# ESP_IOT.net
KiCad netlist of a schematic drawn in Altium Designer
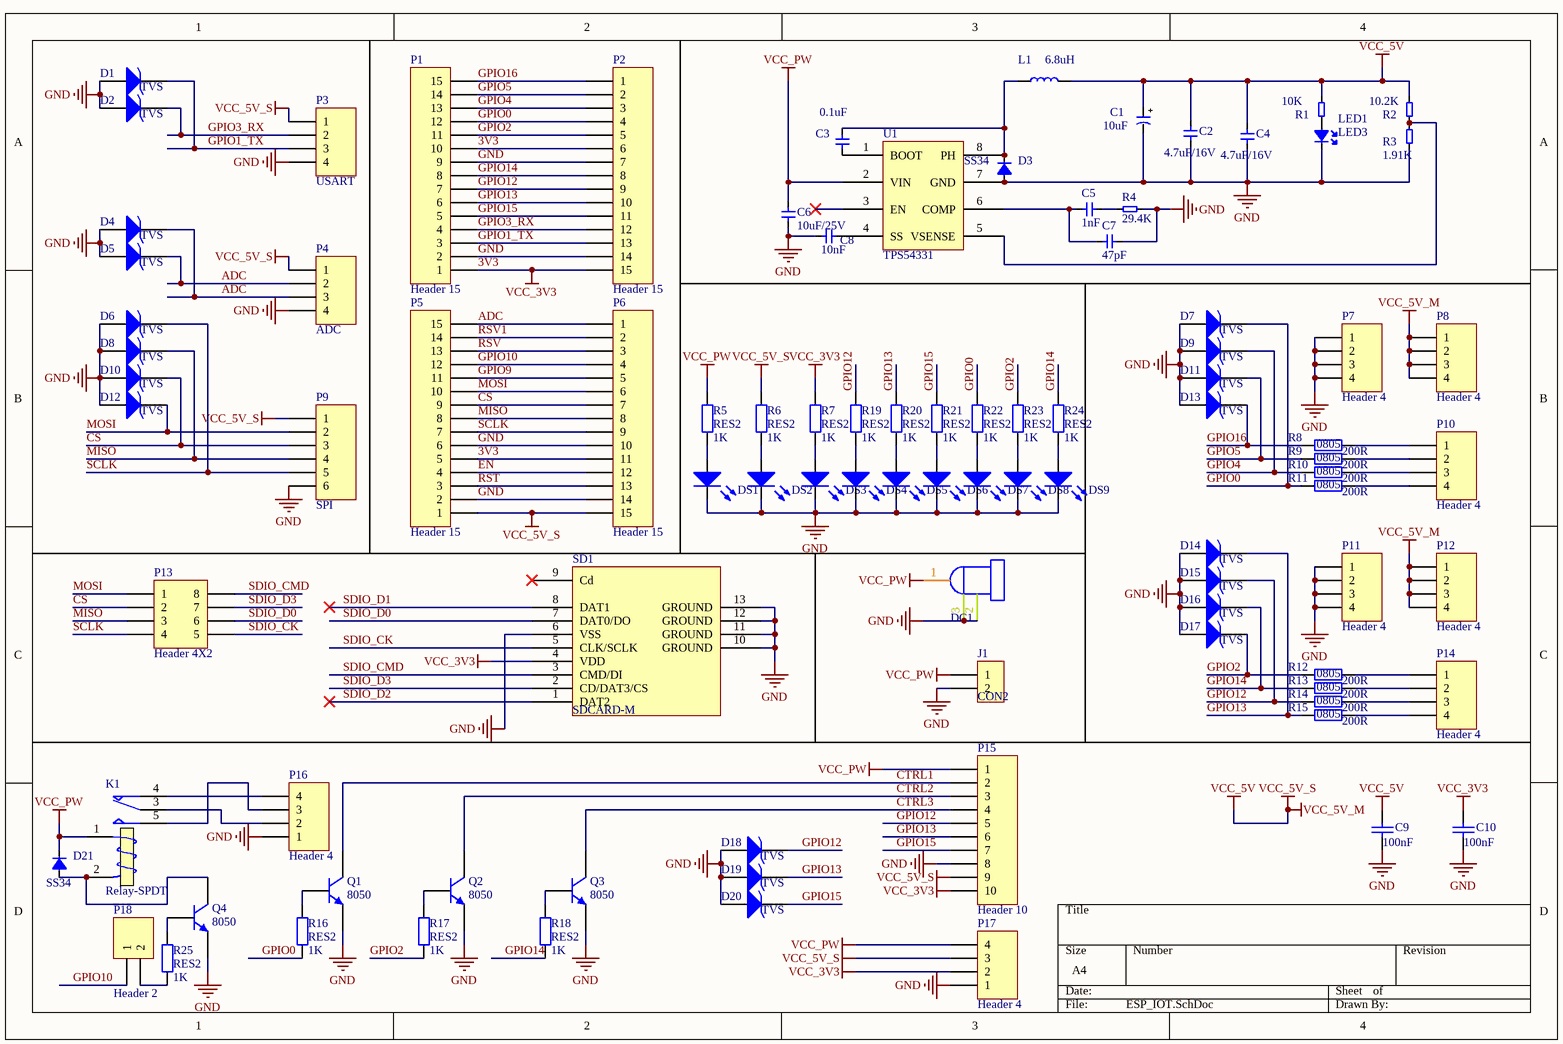
[diagram p0: ESP_IOT.SchDoc]

(export (version "E")
  (design (tool "Eeschema 10.0.6"))
  (components
    (comp (ref "C1")
      (value "10uF")
      (footprint "3528")
      (description "Capacitor")
      (libsource (lib "YHT-SCH") (part "CAP-+"))
    )
    (comp (ref "C2")
      (value "4.7uF/16V")
      (footprint "0603C")
      (description "Capacitor")
      (libsource (lib "YHT-PCB") (part "CAP"))
    )
    (comp (ref "C3")
      (value "0.1uF")
      (footprint "0603C")
      (description "Capacitor")
      (libsource (lib "HXT-SCH") (part "CAP1"))
    )
    (comp (ref "C4")
      (value "4.7uF/16V")
      (footprint "0603C")
      (description "Capacitor")
      (libsource (lib "YHT-PCB") (part "CAP"))
    )
    (comp (ref "C5")
      (value "1nF")
      (footprint "0603C")
      (description "Capacitor")
      (libsource (lib "HXT-SCH") (part "CAP1"))
    )
    (comp (ref "C6")
      (value "10uF/25V")
      (footprint "1206")
      (description "Capacitor")
      (libsource (lib "HXT-SCH") (part "CAP1"))
    )
    (comp (ref "C7")
      (value "47pF")
      (footprint "0603C")
      (description "Capacitor")
      (libsource (lib "YHT-PCB") (part "CAP"))
    )
    (comp (ref "C8")
      (value "10nF")
      (footprint "0603C")
      (description "Capacitor")
      (libsource (lib "YHT-PCB") (part "CAP"))
    )
    (comp (ref "C9")
      (value "100nF")
      (footprint "C 0603_L")
      (fields (field (name "Comment") "CAP"))
      (libsource (lib "QT") (part "CAP"))
    )
    (comp (ref "C10")
      (value "100nF")
      (footprint "C 0603_L")
      (fields (field (name "Comment") "CAP"))
      (libsource (lib "QT") (part "CAP"))
    )
    (comp (ref "D1")
      (value "TVS")
      (footprint "SOD-523")
      (description "High Conductance Fast Diode")
      (fields (field (name "PUBLISHER") "Altium Limited"))
      (libsource (lib "QT") (part "D"))
    )
    (comp (ref "D2")
      (value "TVS")
      (footprint "SOD-523")
      (description "High Conductance Fast Diode")
      (fields (field (name "PUBLISHER") "Altium Limited"))
      (libsource (lib "QT") (part "D"))
    )
    (comp (ref "D3")
      (value "SS34")
      (footprint "DO-214AC-SMA")
      (description "DIODE LED")
      (libsource (lib "HXT-SCH") (part "DIOLED_1"))
    )
    (comp (ref "D4")
      (value "TVS")
      (footprint "SOD-523")
      (description "High Conductance Fast Diode")
      (fields (field (name "PUBLISHER") "Altium Limited"))
      (libsource (lib "QT") (part "D"))
    )
    (comp (ref "D5")
      (value "TVS")
      (footprint "SOD-523")
      (description "High Conductance Fast Diode")
      (fields (field (name "PUBLISHER") "Altium Limited"))
      (libsource (lib "QT") (part "D"))
    )
    (comp (ref "D6")
      (value "TVS")
      (footprint "SOD-523")
      (description "High Conductance Fast Diode")
      (fields (field (name "PUBLISHER") "Altium Limited"))
      (libsource (lib "QT") (part "D"))
    )
    (comp (ref "D7")
      (value "TVS")
      (footprint "SOD-523")
      (description "High Conductance Fast Diode")
      (fields (field (name "PUBLISHER") "Altium Limited"))
      (libsource (lib "QT") (part "D"))
    )
    (comp (ref "D8")
      (value "TVS")
      (footprint "SOD-523")
      (description "High Conductance Fast Diode")
      (fields (field (name "PUBLISHER") "Altium Limited"))
      (libsource (lib "QT") (part "D"))
    )
    (comp (ref "D9")
      (value "TVS")
      (footprint "SOD-523")
      (description "High Conductance Fast Diode")
      (fields (field (name "PUBLISHER") "Altium Limited"))
      (libsource (lib "QT") (part "D"))
    )
    (comp (ref "D10")
      (value "TVS")
      (footprint "SOD-523")
      (description "High Conductance Fast Diode")
      (fields (field (name "PUBLISHER") "Altium Limited"))
      (libsource (lib "QT") (part "D"))
    )
    (comp (ref "D11")
      (value "TVS")
      (footprint "SOD-523")
      (description "High Conductance Fast Diode")
      (fields (field (name "PUBLISHER") "Altium Limited"))
      (libsource (lib "QT") (part "D"))
    )
    (comp (ref "D12")
      (value "TVS")
      (footprint "SOD-523")
      (description "High Conductance Fast Diode")
      (fields (field (name "PUBLISHER") "Altium Limited"))
      (libsource (lib "QT") (part "D"))
    )
    (comp (ref "D13")
      (value "TVS")
      (footprint "SOD-523")
      (description "High Conductance Fast Diode")
      (fields (field (name "PUBLISHER") "Altium Limited"))
      (libsource (lib "QT") (part "D"))
    )
    (comp (ref "D14")
      (value "TVS")
      (footprint "SOD-523")
      (description "High Conductance Fast Diode")
      (fields (field (name "PUBLISHER") "Altium Limited"))
      (libsource (lib "QT") (part "D"))
    )
    (comp (ref "D15")
      (value "TVS")
      (footprint "SOD-523")
      (description "High Conductance Fast Diode")
      (fields (field (name "PUBLISHER") "Altium Limited"))
      (libsource (lib "QT") (part "D"))
    )
    (comp (ref "D16")
      (value "TVS")
      (footprint "SOD-523")
      (description "High Conductance Fast Diode")
      (fields (field (name "PUBLISHER") "Altium Limited"))
      (libsource (lib "QT") (part "D"))
    )
    (comp (ref "D17")
      (value "TVS")
      (footprint "SOD-523")
      (description "High Conductance Fast Diode")
      (fields (field (name "PUBLISHER") "Altium Limited"))
      (libsource (lib "QT") (part "D"))
    )
    (comp (ref "D18")
      (value "TVS")
      (footprint "SOD-523")
      (description "High Conductance Fast Diode")
      (fields (field (name "PUBLISHER") "Altium Limited"))
      (libsource (lib "QT") (part "D"))
    )
    (comp (ref "D19")
      (value "TVS")
      (footprint "SOD-523")
      (description "High Conductance Fast Diode")
      (fields (field (name "PUBLISHER") "Altium Limited"))
      (libsource (lib "QT") (part "D"))
    )
    (comp (ref "D20")
      (value "TVS")
      (footprint "SOD-523")
      (description "High Conductance Fast Diode")
      (fields (field (name "PUBLISHER") "Altium Limited"))
      (libsource (lib "QT") (part "D"))
    )
    (comp (ref "D21")
      (value "SS34")
      (footprint "DO-214AC-SMA")
      (description "DIODE LED")
      (libsource (lib "HXT-SCH") (part "DIOLED_1"))
    )
    (comp (ref "DC1") (value "DC") (footprint "DC-005") (libsource (lib "QT") (part "DC")))
    (comp (ref "DS1") (value "LED") (footprint "LED 0805B") (libsource (lib "QT") (part "LED")))
    (comp (ref "DS2") (value "LED") (footprint "LED 0805B") (libsource (lib "QT") (part "LED")))
    (comp (ref "DS3") (value "LED") (footprint "LED 0805B") (libsource (lib "QT") (part "LED")))
    (comp (ref "DS4") (value "LED") (footprint "LED 0805B") (libsource (lib "QT") (part "LED")))
    (comp (ref "DS5") (value "LED") (footprint "LED 0805B") (libsource (lib "QT") (part "LED")))
    (comp (ref "DS6") (value "LED") (footprint "LED 0805B") (libsource (lib "QT") (part "LED")))
    (comp (ref "DS7") (value "LED") (footprint "LED 0805B") (libsource (lib "QT") (part "LED")))
    (comp (ref "DS8") (value "LED") (footprint "LED 0805B") (libsource (lib "QT") (part "LED")))
    (comp (ref "DS9") (value "LED") (footprint "LED 0805B") (libsource (lib "QT") (part "LED")))
    (comp (ref "J1") (value "CON2") (footprint "DG1282-5.0") (libsource (lib "常用元件库") (part "CON2")))
    (comp (ref "K1")
      (value "Relay-SPDT")
      (footprint "SRD-C_B")
      (description "Single-Pole Dual-Throw Relay")
      (fields (field (name "PUBLISHER") "Altium Limited"))
      (libsource (lib "QT") (part "Relay-SPDT"))
    )
    (comp (ref "L1") (value "6.8uH") (footprint "L100") (libsource (lib "HXT-SCH") (part "INDUCTOR1_1")))
    (comp (ref "LED1")
      (value "LED3")
      (footprint "0603-led")
      (description "DIODE LED")
      (libsource (lib "HXT-SCH") (part "CP_DIOLED"))
    )
    (comp (ref "P1")
      (value "Header 15")
      (footprint "HDR1X15")
      (description "Header, 15-Pin")
      (fields (field (name "PUBLISHER") "Altium Limited"))
      (libsource (lib "Miscellaneous Connectors") (part "Header 15"))
    )
    (comp (ref "P2")
      (value "Header 15")
      (footprint "HDR1X15")
      (description "Header, 15-Pin")
      (fields (field (name "PUBLISHER") "Altium Limited"))
      (libsource (lib "") (part "Header 15_1"))
    )
    (comp (ref "P3")
      (value "USART")
      (footprint "KF2EDGK-2.54-WI-4P")
      (description "Header, 4-Pin")
      (fields (field (name "PUBLISHER") "Altium Limited"))
      (libsource (lib "QT") (part "Header 4"))
    )
    (comp (ref "P4")
      (value "ADC")
      (footprint "KF2EDGK-2.54-WI-4P")
      (description "Header, 4-Pin")
      (fields (field (name "PUBLISHER") "Altium Limited"))
      (libsource (lib "QT") (part "Header 4"))
    )
    (comp (ref "P5")
      (value "Header 15")
      (footprint "HDR1X15")
      (description "Header, 15-Pin")
      (fields (field (name "PUBLISHER") "Altium Limited"))
      (libsource (lib "Miscellaneous Connectors") (part "Header 15"))
    )
    (comp (ref "P6")
      (value "Header 15")
      (footprint "HDR1X15")
      (description "Header, 15-Pin")
      (fields (field (name "PUBLISHER") "Altium Limited"))
      (libsource (lib "") (part "Header 15_1"))
    )
    (comp (ref "P7")
      (value "Header 4")
      (footprint "HDR2.54-LI-4P")
      (description "Header, 4-Pin")
      (fields (field (name "PUBLISHER") "Altium Limited"))
      (libsource (lib "QT") (part "Header 4"))
    )
    (comp (ref "P8")
      (value "Header 4")
      (footprint "HDR2.54-LI-4P")
      (description "Header, 4-Pin")
      (fields (field (name "PUBLISHER") "Altium Limited"))
      (libsource (lib "QT") (part "Header 4"))
    )
    (comp (ref "P9")
      (value "SPI")
      (footprint "KF2EDGK-2.54-WI-6P")
      (description "Header, 6-Pin")
      (fields (field (name "PUBLISHER") "Altium Limited"))
      (libsource (lib "Miscellaneous Connectors") (part "Header 6"))
    )
    (comp (ref "P10")
      (value "Header 4")
      (footprint "HDR2.54-LI-4P")
      (description "Header, 4-Pin")
      (fields (field (name "PUBLISHER") "Altium Limited"))
      (libsource (lib "QT") (part "Header 4"))
    )
    (comp (ref "P11")
      (value "Header 4")
      (footprint "HDR2.54-LI-4P")
      (description "Header, 4-Pin")
      (fields (field (name "PUBLISHER") "Altium Limited"))
      (libsource (lib "QT") (part "Header 4"))
    )
    (comp (ref "P12")
      (value "Header 4")
      (footprint "HDR2.54-LI-4P")
      (description "Header, 4-Pin")
      (fields (field (name "PUBLISHER") "Altium Limited"))
      (libsource (lib "QT") (part "Header 4"))
    )
    (comp (ref "P13")
      (value "Header 4X2")
      (footprint "CSW1.27 SMD-4P")
      (description "Header, 4-Pin, Dual row")
      (fields (field (name "PUBLISHER") "Altium Limited"))
      (libsource (lib "QT") (part "Header 4X2"))
    )
    (comp (ref "P14")
      (value "Header 4")
      (footprint "HDR2.54-LI-4P")
      (description "Header, 4-Pin")
      (fields (field (name "PUBLISHER") "Altium Limited"))
      (libsource (lib "QT") (part "Header 4"))
    )
    (comp (ref "P15")
      (value "Header 10")
      (footprint "KF2EDGK-2.54-WI-10P")
      (description "Header, 10-Pin")
      (fields (field (name "PUBLISHER") "Altium Limited"))
      (libsource (lib "Miscellaneous Connectors") (part "Header 10"))
    )
    (comp (ref "P16")
      (value "Header 4")
      (footprint "COM4_8")
      (description "Header, 4-Pin")
      (fields (field (name "PUBLISHER") "Altium Limited"))
      (libsource (lib "Miscellaneous Connectors") (part "Header 4"))
    )
    (comp (ref "P17")
      (value "Header 4")
      (footprint "COM4_8")
      (description "Header, 4-Pin")
      (fields (field (name "PUBLISHER") "Altium Limited"))
      (libsource (lib "Miscellaneous Connectors") (part "Header 4"))
    )
    (comp (ref "P18")
      (value "Header 2")
      (footprint "HDR2.54-LI-2P")
      (description "Header, 2-Pin")
      (fields (field (name "PUBLISHER") "Altium Limited"))
      (libsource (lib "QT") (part "Header 2"))
    )
    (comp (ref "Q1")
      (value "8050")
      (footprint "SOT23-3L")
      (description "NPN Bipolar Transistor")
      (fields (field (name "PUBLISHER") "Altium Limited"))
      (libsource (lib "QT") (part "NPN  SOT"))
    )
    (comp (ref "Q2")
      (value "8050")
      (footprint "SOT23-3L")
      (description "NPN Bipolar Transistor")
      (fields (field (name "PUBLISHER") "Altium Limited"))
      (libsource (lib "QT") (part "NPN  SOT"))
    )
    (comp (ref "Q3")
      (value "8050")
      (footprint "SOT23-3L")
      (description "NPN Bipolar Transistor")
      (fields (field (name "PUBLISHER") "Altium Limited"))
      (libsource (lib "QT") (part "NPN  SOT"))
    )
    (comp (ref "Q4")
      (value "8050")
      (footprint "SOT23-3L")
      (description "NPN Bipolar Transistor")
      (fields (field (name "PUBLISHER") "Altium Limited"))
      (libsource (lib "QT") (part "NPN  SOT"))
    )
    (comp (ref "R1") (value "10K") (footprint "0603") (libsource (lib "HXT-SCH") (part "RES2")))
    (comp (ref "R2") (value "10.2K") (footprint "0603") (libsource (lib "HXT-SCH") (part "RES2")))
    (comp (ref "R3") (value "1.91K") (footprint "0603") (libsource (lib "HXT-SCH") (part "RES2")))
    (comp (ref "R4") (value "29.4K") (footprint "0603") (libsource (lib "HXT-SCH") (part "RES2")))
    (comp (ref "R5")
      (value "RES2")
      (footprint "R 0805_L")
      (description "Resistor")
      (fields (field (name "ALTIUM_VALUE") "1K") (field (name "PUBLISHER") "Altium Limited"))
      (libsource (lib "") (part "RES2_1"))
    )
    (comp (ref "R6")
      (value "RES2")
      (footprint "R 0805_L")
      (description "Resistor")
      (fields (field (name "ALTIUM_VALUE") "1K") (field (name "PUBLISHER") "Altium Limited"))
      (libsource (lib "") (part "RES2_1"))
    )
    (comp (ref "R7")
      (value "RES2")
      (footprint "R 0805_L")
      (description "Resistor")
      (fields (field (name "ALTIUM_VALUE") "1K") (field (name "PUBLISHER") "Altium Limited"))
      (libsource (lib "") (part "RES2_1"))
    )
    (comp (ref "R8")
      (value "0805")
      (footprint "R 0805_L")
      (description "Resistor")
      (fields (field (name "ALTIUM_VALUE") "200R") (field (name "PUBLISHER") "Altium Limited"))
      (libsource (lib "") (part "RES2_2"))
    )
    (comp (ref "R9")
      (value "0805")
      (footprint "R 0805_L")
      (description "Resistor")
      (fields (field (name "ALTIUM_VALUE") "200R") (field (name "PUBLISHER") "Altium Limited"))
      (libsource (lib "") (part "RES2_2"))
    )
    (comp (ref "R10")
      (value "0805")
      (footprint "R 0805_L")
      (description "Resistor")
      (fields (field (name "ALTIUM_VALUE") "200R") (field (name "PUBLISHER") "Altium Limited"))
      (libsource (lib "") (part "RES2_2"))
    )
    (comp (ref "R11")
      (value "0805")
      (footprint "R 0805_L")
      (description "Resistor")
      (fields (field (name "ALTIUM_VALUE") "200R") (field (name "PUBLISHER") "Altium Limited"))
      (libsource (lib "") (part "RES2_2"))
    )
    (comp (ref "R12")
      (value "0805")
      (footprint "R 0805_L")
      (description "Resistor")
      (fields (field (name "ALTIUM_VALUE") "200R") (field (name "PUBLISHER") "Altium Limited"))
      (libsource (lib "") (part "RES2_2"))
    )
    (comp (ref "R13")
      (value "0805")
      (footprint "R 0805_L")
      (description "Resistor")
      (fields (field (name "ALTIUM_VALUE") "200R") (field (name "PUBLISHER") "Altium Limited"))
      (libsource (lib "") (part "RES2_2"))
    )
    (comp (ref "R14")
      (value "0805")
      (footprint "R 0805_L")
      (description "Resistor")
      (fields (field (name "ALTIUM_VALUE") "200R") (field (name "PUBLISHER") "Altium Limited"))
      (libsource (lib "") (part "RES2_2"))
    )
    (comp (ref "R15")
      (value "0805")
      (footprint "R 0805_L")
      (description "Resistor")
      (fields (field (name "ALTIUM_VALUE") "200R") (field (name "PUBLISHER") "Altium Limited"))
      (libsource (lib "") (part "RES2_2"))
    )
    (comp (ref "R16")
      (value "RES2")
      (footprint "R 0805_L")
      (description "Resistor")
      (fields (field (name "ALTIUM_VALUE") "1K") (field (name "PUBLISHER") "Altium Limited"))
      (libsource (lib "QT") (part "RES2"))
    )
    (comp (ref "R17")
      (value "RES2")
      (footprint "R 0805_L")
      (description "Resistor")
      (fields (field (name "ALTIUM_VALUE") "1K") (field (name "PUBLISHER") "Altium Limited"))
      (libsource (lib "QT") (part "RES2"))
    )
    (comp (ref "R18")
      (value "RES2")
      (footprint "R 0805_L")
      (description "Resistor")
      (fields (field (name "ALTIUM_VALUE") "1K") (field (name "PUBLISHER") "Altium Limited"))
      (libsource (lib "QT") (part "RES2"))
    )
    (comp (ref "R19")
      (value "RES2")
      (footprint "R 0805_L")
      (description "Resistor")
      (fields (field (name "ALTIUM_VALUE") "1K") (field (name "PUBLISHER") "Altium Limited"))
      (libsource (lib "") (part "RES2_1"))
    )
    (comp (ref "R20")
      (value "RES2")
      (footprint "R 0805_L")
      (description "Resistor")
      (fields (field (name "ALTIUM_VALUE") "1K") (field (name "PUBLISHER") "Altium Limited"))
      (libsource (lib "") (part "RES2_1"))
    )
    (comp (ref "R21")
      (value "RES2")
      (footprint "R 0805_L")
      (description "Resistor")
      (fields (field (name "ALTIUM_VALUE") "1K") (field (name "PUBLISHER") "Altium Limited"))
      (libsource (lib "") (part "RES2_1"))
    )
    (comp (ref "R22")
      (value "RES2")
      (footprint "R 0805_L")
      (description "Resistor")
      (fields (field (name "ALTIUM_VALUE") "1K") (field (name "PUBLISHER") "Altium Limited"))
      (libsource (lib "") (part "RES2_1"))
    )
    (comp (ref "R23")
      (value "RES2")
      (footprint "R 0805_L")
      (description "Resistor")
      (fields (field (name "ALTIUM_VALUE") "1K") (field (name "PUBLISHER") "Altium Limited"))
      (libsource (lib "") (part "RES2_1"))
    )
    (comp (ref "R24")
      (value "RES2")
      (footprint "R 0805_L")
      (description "Resistor")
      (fields (field (name "ALTIUM_VALUE") "1K") (field (name "PUBLISHER") "Altium Limited"))
      (libsource (lib "") (part "RES2_1"))
    )
    (comp (ref "R25")
      (value "RES2")
      (footprint "R 0805_L")
      (description "Resistor")
      (fields (field (name "ALTIUM_VALUE") "1K") (field (name "PUBLISHER") "Altium Limited"))
      (libsource (lib "QT") (part "RES2"))
    )
    (comp (ref "SD1")
      (value "SDCARD-M")
      (footprint "SDCARD-M")
      (description "TF卡槽")
      (libsource (lib "Fszhang") (part "SDCARD-M"))
    )
    (comp (ref "U1") (value "TPS54331") (footprint "SO08") (libsource (lib "YHT-SCH") (part "TPS54331")))
  )
  (nets
    (net (code "1") (name "/ADC") (class "Default")
      (node (ref "D4") (pin "2") (pinfunction "K_2") (pintype "passive"))
      (node (ref "D5") (pin "2") (pinfunction "K_2") (pintype "passive"))
      (node (ref "P4") (pin "2") (pinfunction "2_2") (pintype "passive"))
      (node (ref "P4") (pin "3") (pinfunction "3_3") (pintype "passive"))
      (node (ref "P5") (pin "15") (pinfunction "15_15") (pintype "passive"))
      (node (ref "P6") (pin "1") (pinfunction "1_1") (pintype "passive"))
    )
    (net (code "2") (name "/CS") (class "Default")
      (node (ref "D10") (pin "2") (pinfunction "K_2") (pintype "passive"))
      (node (ref "P13") (pin "2") (pinfunction "2_2") (pintype "passive"))
      (node (ref "P5") (pin "9") (pinfunction "9_9") (pintype "passive"))
      (node (ref "P6") (pin "7") (pinfunction "7_7") (pintype "passive"))
      (node (ref "P9") (pin "3") (pinfunction "3_3") (pintype "passive"))
    )
    (net (code "3") (name "/CTRL1") (class "Default")
      (node (ref "P15") (pin "2") (pinfunction "2_2") (pintype "passive"))
      (node (ref "Q1") (pin "3") (pinfunction "C_3") (pintype "passive"))
    )
    (net (code "4") (name "/CTRL2") (class "Default")
      (node (ref "P15") (pin "3") (pinfunction "3_3") (pintype "passive"))
      (node (ref "Q2") (pin "3") (pinfunction "C_3") (pintype "passive"))
    )
    (net (code "5") (name "/CTRL3") (class "Default")
      (node (ref "P15") (pin "4") (pinfunction "4_4") (pintype "passive"))
      (node (ref "Q3") (pin "3") (pinfunction "C_3") (pintype "passive"))
    )
    (net (code "6") (name "/EN") (class "Default")
      (node (ref "P5") (pin "4") (pinfunction "4_4") (pintype "passive"))
      (node (ref "P6") (pin "12") (pinfunction "12_12") (pintype "passive"))
    )
    (net (code "7") (name "/GPIO0") (class "Default")
      (node (ref "D7") (pin "2") (pinfunction "K_2") (pintype "passive"))
      (node (ref "P1") (pin "12") (pinfunction "12_12") (pintype "passive"))
      (node (ref "P2") (pin "4") (pinfunction "4_4") (pintype "passive"))
      (node (ref "R11") (pin "1") (pinfunction "1_1") (pintype "passive"))
      (node (ref "R16") (pin "2") (pinfunction "2_2") (pintype "passive"))
      (node (ref "R22") (pin "2") (pinfunction "2_2") (pintype "passive"))
    )
    (net (code "8") (name "/GPIO1_TX") (class "Default")
      (node (ref "D1") (pin "2") (pinfunction "K_2") (pintype "passive"))
      (node (ref "P1") (pin "3") (pinfunction "3_3") (pintype "passive"))
      (node (ref "P2") (pin "13") (pinfunction "13_13") (pintype "passive"))
      (node (ref "P3") (pin "3") (pinfunction "3_3") (pintype "passive"))
    )
    (net (code "9") (name "/GPIO2") (class "Default")
      (node (ref "D17") (pin "2") (pinfunction "K_2") (pintype "passive"))
      (node (ref "P1") (pin "11") (pinfunction "11_11") (pintype "passive"))
      (node (ref "P2") (pin "5") (pinfunction "5_5") (pintype "passive"))
      (node (ref "R12") (pin "1") (pinfunction "1_1") (pintype "passive"))
      (node (ref "R17") (pin "2") (pinfunction "2_2") (pintype "passive"))
      (node (ref "R23") (pin "2") (pinfunction "2_2") (pintype "passive"))
    )
    (net (code "10") (name "/GPIO3_RX") (class "Default")
      (node (ref "D2") (pin "2") (pinfunction "K_2") (pintype "passive"))
      (node (ref "P1") (pin "4") (pinfunction "4_4") (pintype "passive"))
      (node (ref "P2") (pin "12") (pinfunction "12_12") (pintype "passive"))
      (node (ref "P3") (pin "2") (pinfunction "2_2") (pintype "passive"))
    )
    (net (code "11") (name "/GPIO4") (class "Default")
      (node (ref "D9") (pin "2") (pinfunction "K_2") (pintype "passive"))
      (node (ref "P1") (pin "13") (pinfunction "13_13") (pintype "passive"))
      (node (ref "P2") (pin "3") (pinfunction "3_3") (pintype "passive"))
      (node (ref "R10") (pin "1") (pinfunction "1_1") (pintype "passive"))
    )
    (net (code "12") (name "/GPIO5") (class "Default")
      (node (ref "D11") (pin "2") (pinfunction "K_2") (pintype "passive"))
      (node (ref "P1") (pin "14") (pinfunction "14_14") (pintype "passive"))
      (node (ref "P2") (pin "2") (pinfunction "2_2") (pintype "passive"))
      (node (ref "R9") (pin "1") (pinfunction "1_1") (pintype "passive"))
    )
    (net (code "13") (name "/GPIO9") (class "Default")
      (node (ref "P5") (pin "11") (pinfunction "11_11") (pintype "passive"))
      (node (ref "P6") (pin "5") (pinfunction "5_5") (pintype "passive"))
    )
    (net (code "14") (name "/GPIO10") (class "Default")
      (node (ref "P18") (pin "1") (pinfunction "1_1") (pintype "passive"))
      (node (ref "P5") (pin "12") (pinfunction "12_12") (pintype "passive"))
      (node (ref "P6") (pin "4") (pinfunction "4_4") (pintype "passive"))
    )
    (net (code "15") (name "/GPIO12") (class "Default")
      (node (ref "D15") (pin "2") (pinfunction "K_2") (pintype "passive"))
      (node (ref "D18") (pin "2") (pinfunction "K_2") (pintype "passive"))
      (node (ref "P1") (pin "7") (pinfunction "7_7") (pintype "passive"))
      (node (ref "P15") (pin "5") (pinfunction "5_5") (pintype "passive"))
      (node (ref "P2") (pin "9") (pinfunction "9_9") (pintype "passive"))
      (node (ref "R14") (pin "1") (pinfunction "1_1") (pintype "passive"))
      (node (ref "R19") (pin "2") (pinfunction "2_2") (pintype "passive"))
    )
    (net (code "16") (name "/GPIO13") (class "Default")
      (node (ref "D14") (pin "2") (pinfunction "K_2") (pintype "passive"))
      (node (ref "D19") (pin "2") (pinfunction "K_2") (pintype "passive"))
      (node (ref "P1") (pin "6") (pinfunction "6_6") (pintype "passive"))
      (node (ref "P15") (pin "6") (pinfunction "6_6") (pintype "passive"))
      (node (ref "P2") (pin "10") (pinfunction "10_10") (pintype "passive"))
      (node (ref "R15") (pin "1") (pinfunction "1_1") (pintype "passive"))
      (node (ref "R20") (pin "2") (pinfunction "2_2") (pintype "passive"))
    )
    (net (code "17") (name "/GPIO14") (class "Default")
      (node (ref "D16") (pin "2") (pinfunction "K_2") (pintype "passive"))
      (node (ref "P1") (pin "8") (pinfunction "8_8") (pintype "passive"))
      (node (ref "P2") (pin "8") (pinfunction "8_8") (pintype "passive"))
      (node (ref "R13") (pin "1") (pinfunction "1_1") (pintype "passive"))
      (node (ref "R18") (pin "2") (pinfunction "2_2") (pintype "passive"))
      (node (ref "R24") (pin "2") (pinfunction "2_2") (pintype "passive"))
    )
    (net (code "18") (name "/GPIO15") (class "Default")
      (node (ref "D20") (pin "2") (pinfunction "K_2") (pintype "passive"))
      (node (ref "P1") (pin "5") (pinfunction "5_5") (pintype "passive"))
      (node (ref "P15") (pin "7") (pinfunction "7_7") (pintype "passive"))
      (node (ref "P2") (pin "11") (pinfunction "11_11") (pintype "passive"))
      (node (ref "R21") (pin "2") (pinfunction "2_2") (pintype "passive"))
    )
    (net (code "19") (name "/GPIO16") (class "Default")
      (node (ref "D13") (pin "2") (pinfunction "K_2") (pintype "passive"))
      (node (ref "P1") (pin "15") (pinfunction "15_15") (pintype "passive"))
      (node (ref "P2") (pin "1") (pinfunction "1_1") (pintype "passive"))
      (node (ref "R8") (pin "1") (pinfunction "1_1") (pintype "passive"))
    )
    (net (code "20") (name "/MISO") (class "Default")
      (node (ref "D8") (pin "2") (pinfunction "K_2") (pintype "passive"))
      (node (ref "P13") (pin "3") (pinfunction "3_3") (pintype "passive"))
      (node (ref "P5") (pin "8") (pinfunction "8_8") (pintype "passive"))
      (node (ref "P6") (pin "8") (pinfunction "8_8") (pintype "passive"))
      (node (ref "P9") (pin "4") (pinfunction "4_4") (pintype "passive"))
    )
    (net (code "21") (name "/MOSI") (class "Default")
      (node (ref "D12") (pin "2") (pinfunction "K_2") (pintype "passive"))
      (node (ref "P13") (pin "1") (pinfunction "1_1") (pintype "passive"))
      (node (ref "P5") (pin "10") (pinfunction "10_10") (pintype "passive"))
      (node (ref "P6") (pin "6") (pinfunction "6_6") (pintype "passive"))
      (node (ref "P9") (pin "2") (pinfunction "2_2") (pintype "passive"))
    )
    (net (code "22") (name "/RST") (class "Default")
      (node (ref "P5") (pin "3") (pinfunction "3_3") (pintype "passive"))
      (node (ref "P6") (pin "13") (pinfunction "13_13") (pintype "passive"))
    )
    (net (code "23") (name "/RSV") (class "Default")
      (node (ref "P5") (pin "13") (pinfunction "13_13") (pintype "passive"))
      (node (ref "P6") (pin "3") (pinfunction "3_3") (pintype "passive"))
    )
    (net (code "24") (name "/RSV1") (class "Default")
      (node (ref "P5") (pin "14") (pinfunction "14_14") (pintype "passive"))
      (node (ref "P6") (pin "2") (pinfunction "2_2") (pintype "passive"))
    )
    (net (code "25") (name "/SCLK") (class "Default")
      (node (ref "D6") (pin "2") (pinfunction "K_2") (pintype "passive"))
      (node (ref "P13") (pin "4") (pinfunction "4_4") (pintype "passive"))
      (node (ref "P5") (pin "7") (pinfunction "7_7") (pintype "passive"))
      (node (ref "P6") (pin "9") (pinfunction "9_9") (pintype "passive"))
      (node (ref "P9") (pin "5") (pinfunction "5_5") (pintype "passive"))
    )
    (net (code "26") (name "/SDIO_CK") (class "Default")
      (node (ref "P13") (pin "5") (pinfunction "5_5") (pintype "passive"))
      (node (ref "SD1") (pin "5") (pinfunction "CLK/SCLK_5") (pintype "passive"))
    )
    (net (code "27") (name "/SDIO_CMD") (class "Default")
      (node (ref "P13") (pin "8") (pinfunction "8_8") (pintype "passive"))
      (node (ref "SD1") (pin "3") (pinfunction "CMD/DI_3") (pintype "passive"))
    )
    (net (code "28") (name "/SDIO_D0") (class "Default")
      (node (ref "P13") (pin "6") (pinfunction "6_6") (pintype "passive"))
      (node (ref "SD1") (pin "7") (pinfunction "DAT0/DO_7") (pintype "passive"))
    )
    (net (code "29") (name "/SDIO_D1") (class "Default")
      (node (ref "SD1") (pin "8") (pinfunction "DAT1_8") (pintype "passive+no_connect"))
    )
    (net (code "30") (name "/SDIO_D2") (class "Default")
      (node (ref "SD1") (pin "1") (pinfunction "DAT2_1") (pintype "passive+no_connect"))
    )
    (net (code "31") (name "/SDIO_D3") (class "Default")
      (node (ref "P13") (pin "7") (pinfunction "7_7") (pintype "passive"))
      (node (ref "SD1") (pin "2") (pinfunction "CD/DAT3/CS_2") (pintype "passive"))
    )
    (net (code "32") (name "GND") (class "Default")
      (node (ref "C1") (pin "2") (pinfunction "2_2") (pintype "passive"))
      (node (ref "C10") (pin "1") (pinfunction "1_1") (pintype "passive"))
      (node (ref "C2") (pin "1") (pinfunction "1_1") (pintype "passive"))
      (node (ref "C4") (pin "1") (pinfunction "1_1") (pintype "passive"))
      (node (ref "C6") (pin "1") (pinfunction "1_1") (pintype "passive"))
      (node (ref "C7") (pin "2") (pinfunction "2_2") (pintype "passive"))
      (node (ref "C8") (pin "2") (pinfunction "2_2") (pintype "passive"))
      (node (ref "C9") (pin "1") (pinfunction "1_1") (pintype "passive"))
      (node (ref "D1") (pin "1") (pinfunction "A_1") (pintype "passive"))
      (node (ref "D10") (pin "1") (pinfunction "A_1") (pintype "passive"))
      (node (ref "D11") (pin "1") (pinfunction "A_1") (pintype "passive"))
      (node (ref "D12") (pin "1") (pinfunction "A_1") (pintype "passive"))
      (node (ref "D13") (pin "1") (pinfunction "A_1") (pintype "passive"))
      (node (ref "D14") (pin "1") (pinfunction "A_1") (pintype "passive"))
      (node (ref "D15") (pin "1") (pinfunction "A_1") (pintype "passive"))
      (node (ref "D16") (pin "1") (pinfunction "A_1") (pintype "passive"))
      (node (ref "D17") (pin "1") (pinfunction "A_1") (pintype "passive"))
      (node (ref "D18") (pin "1") (pinfunction "A_1") (pintype "passive"))
      (node (ref "D19") (pin "1") (pinfunction "A_1") (pintype "passive"))
      (node (ref "D2") (pin "1") (pinfunction "A_1") (pintype "passive"))
      (node (ref "D20") (pin "1") (pinfunction "A_1") (pintype "passive"))
      (node (ref "D3") (pin "1") (pinfunction "A_1") (pintype "passive"))
      (node (ref "D4") (pin "1") (pinfunction "A_1") (pintype "passive"))
      (node (ref "D5") (pin "1") (pinfunction "A_1") (pintype "passive"))
      (node (ref "D6") (pin "1") (pinfunction "A_1") (pintype "passive"))
      (node (ref "D7") (pin "1") (pinfunction "A_1") (pintype "passive"))
      (node (ref "D8") (pin "1") (pinfunction "A_1") (pintype "passive"))
      (node (ref "D9") (pin "1") (pinfunction "A_1") (pintype "passive"))
      (node (ref "DC1") (pin "2") (pinfunction "-_2") (pintype "passive"))
      (node (ref "DC1") (pin "3") (pinfunction "-_3") (pintype "passive"))
      (node (ref "DS1") (pin "2") (pinfunction "K_2") (pintype "passive"))
      (node (ref "DS2") (pin "2") (pinfunction "K_2") (pintype "passive"))
      (node (ref "DS3") (pin "2") (pinfunction "K_2") (pintype "passive"))
      (node (ref "DS4") (pin "2") (pinfunction "K_2") (pintype "passive"))
      (node (ref "DS5") (pin "2") (pinfunction "K_2") (pintype "passive"))
      (node (ref "DS6") (pin "2") (pinfunction "K_2") (pintype "passive"))
      (node (ref "DS7") (pin "2") (pinfunction "K_2") (pintype "passive"))
      (node (ref "DS8") (pin "2") (pinfunction "K_2") (pintype "passive"))
      (node (ref "DS9") (pin "2") (pinfunction "K_2") (pintype "passive"))
      (node (ref "J1") (pin "2") (pinfunction "2_2") (pintype "passive"))
      (node (ref "LED1") (pin "2") (pinfunction "K_2") (pintype "passive"))
      (node (ref "P1") (pin "2") (pinfunction "2_2") (pintype "passive"))
      (node (ref "P1") (pin "9") (pinfunction "9_9") (pintype "passive"))
      (node (ref "P11") (pin "1") (pinfunction "1_1") (pintype "passive"))
      (node (ref "P11") (pin "2") (pinfunction "2_2") (pintype "passive"))
      (node (ref "P11") (pin "3") (pinfunction "3_3") (pintype "passive"))
      (node (ref "P11") (pin "4") (pinfunction "4_4") (pintype "passive"))
      (node (ref "P15") (pin "8") (pinfunction "8_8") (pintype "passive"))
      (node (ref "P16") (pin "1") (pinfunction "1_1") (pintype "passive"))
      (node (ref "P17") (pin "1") (pinfunction "1_1") (pintype "passive"))
      (node (ref "P2") (pin "14") (pinfunction "14_14") (pintype "passive"))
      (node (ref "P2") (pin "7") (pinfunction "7_7") (pintype "passive"))
      (node (ref "P3") (pin "4") (pinfunction "4_4") (pintype "passive"))
      (node (ref "P4") (pin "4") (pinfunction "4_4") (pintype "passive"))
      (node (ref "P5") (pin "2") (pinfunction "2_2") (pintype "passive"))
      (node (ref "P5") (pin "6") (pinfunction "6_6") (pintype "passive"))
      (node (ref "P6") (pin "10") (pinfunction "10_10") (pintype "passive"))
      (node (ref "P6") (pin "14") (pinfunction "14_14") (pintype "passive"))
      (node (ref "P7") (pin "1") (pinfunction "1_1") (pintype "passive"))
      (node (ref "P7") (pin "2") (pinfunction "2_2") (pintype "passive"))
      (node (ref "P7") (pin "3") (pinfunction "3_3") (pintype "passive"))
      (node (ref "P7") (pin "4") (pinfunction "4_4") (pintype "passive"))
      (node (ref "P9") (pin "6") (pinfunction "6_6") (pintype "passive"))
      (node (ref "Q1") (pin "2") (pinfunction "E_2") (pintype "passive"))
      (node (ref "Q2") (pin "2") (pinfunction "E_2") (pintype "passive"))
      (node (ref "Q3") (pin "2") (pinfunction "E_2") (pintype "passive"))
      (node (ref "Q4") (pin "2") (pinfunction "E_2") (pintype "passive"))
      (node (ref "R3") (pin "1") (pinfunction "1_1") (pintype "passive"))
      (node (ref "R4") (pin "1") (pinfunction "1_1") (pintype "passive"))
      (node (ref "SD1") (pin "10") (pinfunction "GROUND_10") (pintype "passive"))
      (node (ref "SD1") (pin "11") (pinfunction "GROUND_11") (pintype "passive"))
      (node (ref "SD1") (pin "12") (pinfunction "GROUND_12") (pintype "passive"))
      (node (ref "SD1") (pin "13") (pinfunction "GROUND_13") (pintype "passive"))
      (node (ref "SD1") (pin "6") (pinfunction "VSS_6") (pintype "passive"))
      (node (ref "U1") (pin "7") (pinfunction "GND_7") (pintype "passive"))
    )
    (net (code "33") (name "Net-(C5-Pad1)") (class "Default")
      (node (ref "C5") (pin "1") (pinfunction "1_1") (pintype "passive"))
      (node (ref "R4") (pin "2") (pinfunction "2_2") (pintype "passive"))
    )
    (net (code "34") (name "Net-(D3-K)") (class "Default")
      (node (ref "C3") (pin "2") (pinfunction "2_2") (pintype "passive"))
      (node (ref "D3") (pin "2") (pinfunction "K_2") (pintype "passive"))
      (node (ref "L1") (pin "2") (pinfunction "2_2") (pintype "passive"))
      (node (ref "U1") (pin "8") (pinfunction "PH_8") (pintype "power_in"))
    )
    (net (code "35") (name "Net-(D21-A)") (class "Default")
      (node (ref "D21") (pin "1") (pinfunction "A_1") (pintype "passive"))
      (node (ref "K1") (pin "2") (pinfunction "T2_2") (pintype "passive"))
      (node (ref "Q4") (pin "3") (pinfunction "C_3") (pintype "passive"))
    )
    (net (code "36") (name "Net-(DS1-A)") (class "Default")
      (node (ref "DS1") (pin "1") (pinfunction "A_1") (pintype "passive"))
      (node (ref "R5") (pin "1") (pinfunction "1_1") (pintype "passive"))
    )
    (net (code "37") (name "Net-(DS2-A)") (class "Default")
      (node (ref "DS2") (pin "1") (pinfunction "A_1") (pintype "passive"))
      (node (ref "R6") (pin "1") (pinfunction "1_1") (pintype "passive"))
    )
    (net (code "38") (name "Net-(DS3-A)") (class "Default")
      (node (ref "DS3") (pin "1") (pinfunction "A_1") (pintype "passive"))
      (node (ref "R7") (pin "1") (pinfunction "1_1") (pintype "passive"))
    )
    (net (code "39") (name "Net-(DS4-A)") (class "Default")
      (node (ref "DS4") (pin "1") (pinfunction "A_1") (pintype "passive"))
      (node (ref "R19") (pin "1") (pinfunction "1_1") (pintype "passive"))
    )
    (net (code "40") (name "Net-(DS5-A)") (class "Default")
      (node (ref "DS5") (pin "1") (pinfunction "A_1") (pintype "passive"))
      (node (ref "R20") (pin "1") (pinfunction "1_1") (pintype "passive"))
    )
    (net (code "41") (name "Net-(DS6-A)") (class "Default")
      (node (ref "DS6") (pin "1") (pinfunction "A_1") (pintype "passive"))
      (node (ref "R21") (pin "1") (pinfunction "1_1") (pintype "passive"))
    )
    (net (code "42") (name "Net-(DS7-A)") (class "Default")
      (node (ref "DS7") (pin "1") (pinfunction "A_1") (pintype "passive"))
      (node (ref "R22") (pin "1") (pinfunction "1_1") (pintype "passive"))
    )
    (net (code "43") (name "Net-(DS8-A)") (class "Default")
      (node (ref "DS8") (pin "1") (pinfunction "A_1") (pintype "passive"))
      (node (ref "R23") (pin "1") (pinfunction "1_1") (pintype "passive"))
    )
    (net (code "44") (name "Net-(DS9-A)") (class "Default")
      (node (ref "DS9") (pin "1") (pinfunction "A_1") (pintype "passive"))
      (node (ref "R24") (pin "1") (pinfunction "1_1") (pintype "passive"))
    )
    (net (code "45") (name "Net-(K1-COM)") (class "Default")
      (node (ref "K1") (pin "3") (pinfunction "COM_3") (pintype "passive"))
      (node (ref "P16") (pin "2") (pinfunction "2_2") (pintype "passive"))
    )
    (net (code "46") (name "Net-(K1-NC)") (class "Default")
      (node (ref "K1") (pin "4") (pinfunction "NC_4") (pintype "passive"))
      (node (ref "P16") (pin "4") (pinfunction "4_4") (pintype "passive"))
    )
    (net (code "47") (name "Net-(K1-NO)") (class "Default")
      (node (ref "K1") (pin "5") (pinfunction "NO_5") (pintype "passive"))
      (node (ref "P16") (pin "3") (pinfunction "3_3") (pintype "passive"))
    )
    (net (code "48") (name "Net-(LED1-A)") (class "Default")
      (node (ref "LED1") (pin "1") (pinfunction "A_1") (pintype "passive"))
      (node (ref "R1") (pin "1") (pinfunction "1_1") (pintype "passive"))
    )
    (net (code "49") (name "Net-(P10-Pad1)") (class "Default")
      (node (ref "P10") (pin "1") (pinfunction "1_1") (pintype "passive"))
      (node (ref "R8") (pin "2") (pinfunction "2_2") (pintype "passive"))
    )
    (net (code "50") (name "Net-(P10-Pad2)") (class "Default")
      (node (ref "P10") (pin "2") (pinfunction "2_2") (pintype "passive"))
      (node (ref "R9") (pin "2") (pinfunction "2_2") (pintype "passive"))
    )
    (net (code "51") (name "Net-(P10-Pad3)") (class "Default")
      (node (ref "P10") (pin "3") (pinfunction "3_3") (pintype "passive"))
      (node (ref "R10") (pin "2") (pinfunction "2_2") (pintype "passive"))
    )
    (net (code "52") (name "Net-(P10-Pad4)") (class "Default")
      (node (ref "P10") (pin "4") (pinfunction "4_4") (pintype "passive"))
      (node (ref "R11") (pin "2") (pinfunction "2_2") (pintype "passive"))
    )
    (net (code "53") (name "Net-(P14-Pad1)") (class "Default")
      (node (ref "P14") (pin "1") (pinfunction "1_1") (pintype "passive"))
      (node (ref "R12") (pin "2") (pinfunction "2_2") (pintype "passive"))
    )
    (net (code "54") (name "Net-(P14-Pad2)") (class "Default")
      (node (ref "P14") (pin "2") (pinfunction "2_2") (pintype "passive"))
      (node (ref "R13") (pin "2") (pinfunction "2_2") (pintype "passive"))
    )
    (net (code "55") (name "Net-(P14-Pad3)") (class "Default")
      (node (ref "P14") (pin "3") (pinfunction "3_3") (pintype "passive"))
      (node (ref "R14") (pin "2") (pinfunction "2_2") (pintype "passive"))
    )
    (net (code "56") (name "Net-(P14-Pad4)") (class "Default")
      (node (ref "P14") (pin "4") (pinfunction "4_4") (pintype "passive"))
      (node (ref "R15") (pin "2") (pinfunction "2_2") (pintype "passive"))
    )
    (net (code "57") (name "Net-(P18-Pad2)") (class "Default")
      (node (ref "P18") (pin "2") (pinfunction "2_2") (pintype "passive"))
      (node (ref "R25") (pin "2") (pinfunction "2_2") (pintype "passive"))
    )
    (net (code "58") (name "Net-(Q1-B)") (class "Default")
      (node (ref "Q1") (pin "1") (pinfunction "B_1") (pintype "passive"))
      (node (ref "R16") (pin "1") (pinfunction "1_1") (pintype "passive"))
    )
    (net (code "59") (name "Net-(Q2-B)") (class "Default")
      (node (ref "Q2") (pin "1") (pinfunction "B_1") (pintype "passive"))
      (node (ref "R17") (pin "1") (pinfunction "1_1") (pintype "passive"))
    )
    (net (code "60") (name "Net-(Q3-B)") (class "Default")
      (node (ref "Q3") (pin "1") (pinfunction "B_1") (pintype "passive"))
      (node (ref "R18") (pin "1") (pinfunction "1_1") (pintype "passive"))
    )
    (net (code "61") (name "Net-(Q4-B)") (class "Default")
      (node (ref "Q4") (pin "1") (pinfunction "B_1") (pintype "passive"))
      (node (ref "R25") (pin "1") (pinfunction "1_1") (pintype "passive"))
    )
    (net (code "62") (name "Net-(U1-BOOT)") (class "Default")
      (node (ref "C3") (pin "1") (pinfunction "1_1") (pintype "passive"))
      (node (ref "U1") (pin "1") (pinfunction "BOOT_1") (pintype "passive"))
    )
    (net (code "63") (name "Net-(U1-COMP)") (class "Default")
      (node (ref "C5") (pin "2") (pinfunction "2_2") (pintype "passive"))
      (node (ref "C7") (pin "1") (pinfunction "1_1") (pintype "passive"))
      (node (ref "U1") (pin "6") (pinfunction "COMP_6") (pintype "passive"))
    )
    (net (code "64") (name "Net-(U1-SS)") (class "Default")
      (node (ref "C8") (pin "1") (pinfunction "1_1") (pintype "passive"))
      (node (ref "U1") (pin "4") (pinfunction "SS_4") (pintype "power_in"))
    )
    (net (code "65") (name "Net-(U1-VSENSE)") (class "Default")
      (node (ref "R2") (pin "1") (pinfunction "1_1") (pintype "passive"))
      (node (ref "R3") (pin "2") (pinfunction "2_2") (pintype "passive"))
      (node (ref "U1") (pin "5") (pinfunction "VSENSE_5") (pintype "passive"))
    )
    (net (code "66") (name "VCC_3V3") (class "Default")
      (node (ref "C10") (pin "2") (pinfunction "2_2") (pintype "passive"))
      (node (ref "P1") (pin "1") (pinfunction "1_1") (pintype "passive"))
      (node (ref "P1") (pin "10") (pinfunction "10_10") (pintype "passive"))
      (node (ref "P15") (pin "10") (pinfunction "10_10") (pintype "passive"))
      (node (ref "P17") (pin "2") (pinfunction "2_2") (pintype "passive"))
      (node (ref "P2") (pin "15") (pinfunction "15_15") (pintype "passive"))
      (node (ref "P2") (pin "6") (pinfunction "6_6") (pintype "passive"))
      (node (ref "P5") (pin "5") (pinfunction "5_5") (pintype "passive"))
      (node (ref "P6") (pin "11") (pinfunction "11_11") (pintype "passive"))
      (node (ref "R7") (pin "2") (pinfunction "2_2") (pintype "passive"))
      (node (ref "SD1") (pin "4") (pinfunction "VDD_4") (pintype "passive"))
    )
    (net (code "67") (name "VCC_5V") (class "Default")
      (node (ref "C1") (pin "1") (pinfunction "1_1") (pintype "passive"))
      (node (ref "C2") (pin "2") (pinfunction "2_2") (pintype "passive"))
      (node (ref "C4") (pin "2") (pinfunction "2_2") (pintype "passive"))
      (node (ref "C9") (pin "2") (pinfunction "2_2") (pintype "passive"))
      (node (ref "L1") (pin "1") (pinfunction "1_1") (pintype "passive"))
      (node (ref "P12") (pin "1") (pinfunction "1_1") (pintype "passive"))
      (node (ref "P12") (pin "2") (pinfunction "2_2") (pintype "passive"))
      (node (ref "P12") (pin "3") (pinfunction "3_3") (pintype "passive"))
      (node (ref "P12") (pin "4") (pinfunction "4_4") (pintype "passive"))
      (node (ref "P15") (pin "9") (pinfunction "9_9") (pintype "passive"))
      (node (ref "P17") (pin "3") (pinfunction "3_3") (pintype "passive"))
      (node (ref "P3") (pin "1") (pinfunction "1_1") (pintype "passive"))
      (node (ref "P4") (pin "1") (pinfunction "1_1") (pintype "passive"))
      (node (ref "P5") (pin "1") (pinfunction "1_1") (pintype "passive"))
      (node (ref "P6") (pin "15") (pinfunction "15_15") (pintype "passive"))
      (node (ref "P8") (pin "1") (pinfunction "1_1") (pintype "passive"))
      (node (ref "P8") (pin "2") (pinfunction "2_2") (pintype "passive"))
      (node (ref "P8") (pin "3") (pinfunction "3_3") (pintype "passive"))
      (node (ref "P8") (pin "4") (pinfunction "4_4") (pintype "passive"))
      (node (ref "P9") (pin "1") (pinfunction "1_1") (pintype "passive"))
      (node (ref "R1") (pin "2") (pinfunction "2_2") (pintype "passive"))
      (node (ref "R2") (pin "2") (pinfunction "2_2") (pintype "passive"))
      (node (ref "R6") (pin "2") (pinfunction "2_2") (pintype "passive"))
    )
    (net (code "68") (name "VCC_PW") (class "Default")
      (node (ref "C6") (pin "2") (pinfunction "2_2") (pintype "passive"))
      (node (ref "D21") (pin "2") (pinfunction "K_2") (pintype "passive"))
      (node (ref "DC1") (pin "1") (pinfunction "+_1") (pintype "passive"))
      (node (ref "J1") (pin "1") (pinfunction "1_1") (pintype "passive"))
      (node (ref "K1") (pin "1") (pinfunction "T1_1") (pintype "passive"))
      (node (ref "P15") (pin "1") (pinfunction "1_1") (pintype "passive"))
      (node (ref "P17") (pin "4") (pinfunction "4_4") (pintype "passive"))
      (node (ref "R5") (pin "2") (pinfunction "2_2") (pintype "passive"))
      (node (ref "U1") (pin "2") (pinfunction "VIN_2") (pintype "passive"))
    )
    (net (code "69") (name "unconnected-(SD1-Cd-Pad9)") (class "Default")
      (node (ref "SD1") (pin "9") (pinfunction "Cd_9") (pintype "passive+no_connect"))
    )
    (net (code "70") (name "unconnected-(U1-EN-Pad3)") (class "Default")
      (node (ref "U1") (pin "3") (pinfunction "EN_3") (pintype "passive+no_connect"))
    )
  )
)
